# 9_PCIE3.net
KiCad netlist of a schematic drawn in Altium Designer
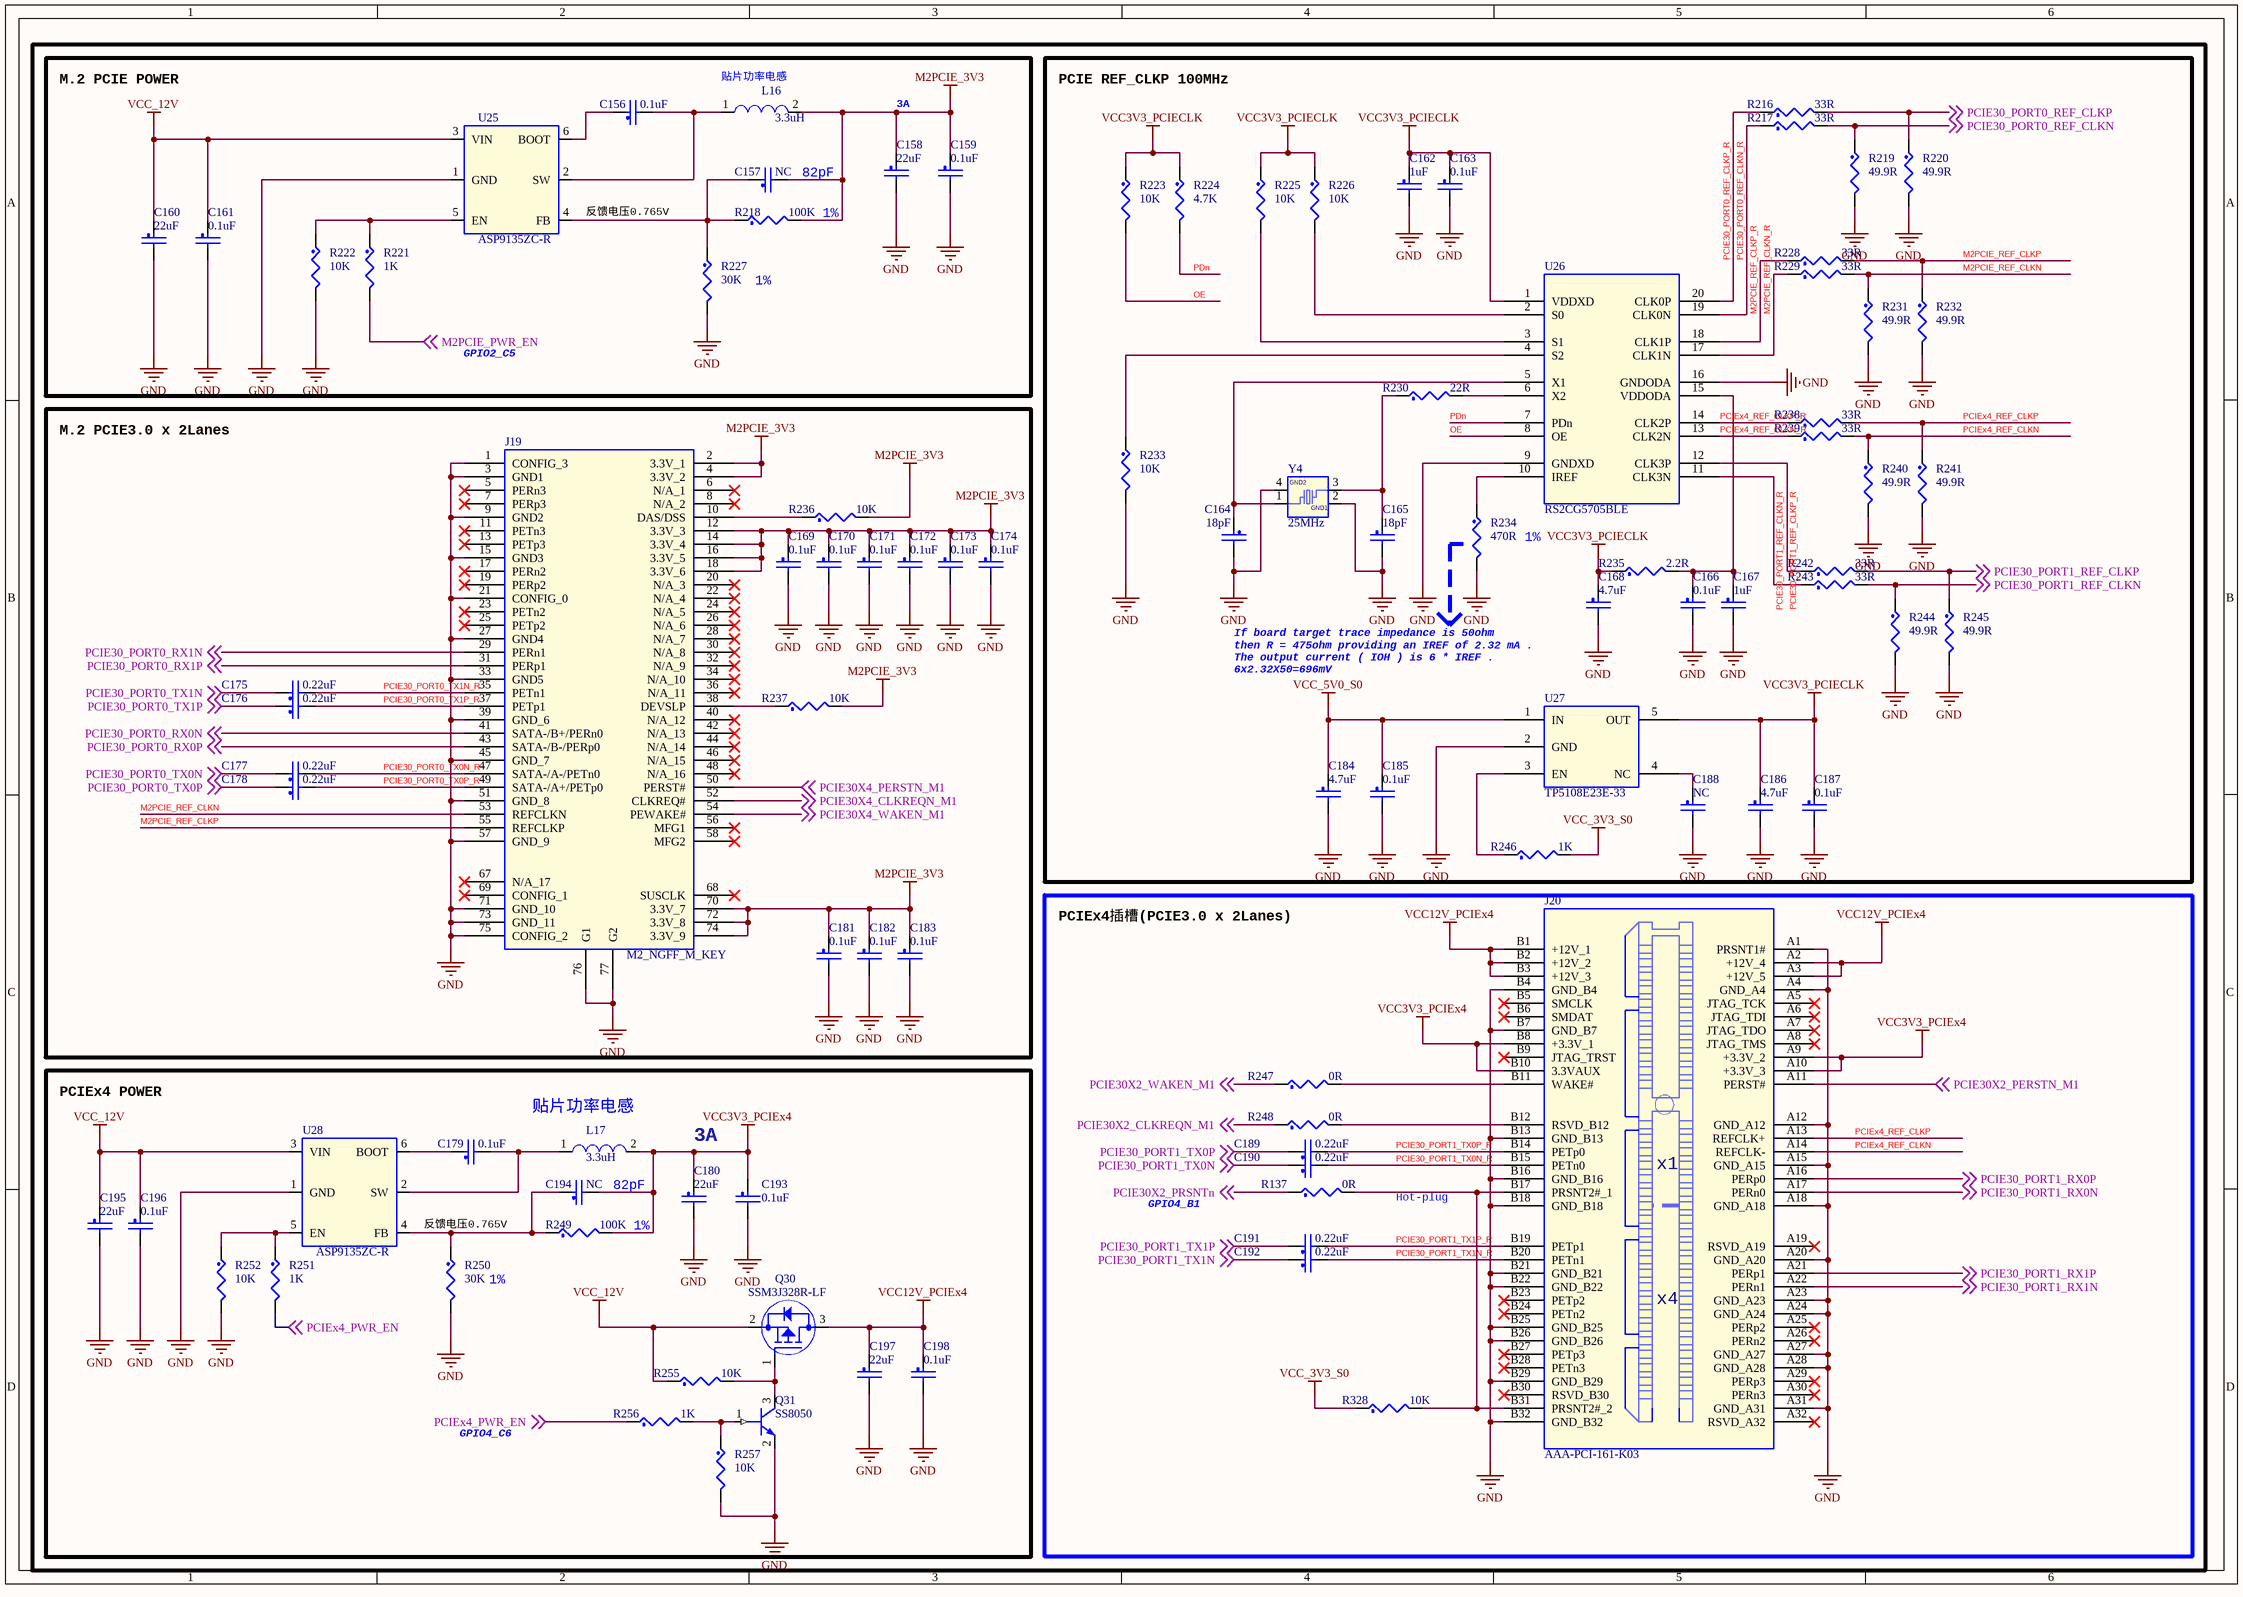
[diagram p0: 9.PCIE3.SchDoc]

(export (version "E")
  (design (tool "Eeschema 10.0.6"))
  (components
    (comp (ref "C156")
      (value "0.1uF")
      (footprint "0.PCB1:C0402")
      (libsource (lib "RK3588底板") (part "CAP_NP"))
    )
    (comp (ref "C157") (value "NC") (footprint "0.PCB1:C0402") (libsource (lib "RK3588底板") (part "CAP_NP")))
    (comp (ref "C158") (value "22uF") (footprint "0.PCB1:C0603") (libsource (lib "RK3588底板") (part "CAP_NP")))
    (comp (ref "C159")
      (value "0.1uF")
      (footprint "0.PCB1:C0402")
      (libsource (lib "RK3588底板") (part "CAP_NP"))
    )
    (comp (ref "C160") (value "22uF") (footprint "0.PCB1:C0603") (libsource (lib "RK3588底板") (part "CAP_NP")))
    (comp (ref "C161")
      (value "0.1uF")
      (footprint "0.PCB1:C0402")
      (libsource (lib "RK3588底板") (part "CAP_NP"))
    )
    (comp (ref "C162") (value "1uF") (footprint "0.PCB1:C0402") (libsource (lib "RK3588底板") (part "CAP_NP")))
    (comp (ref "C163")
      (value "0.1uF")
      (footprint "0.PCB1:C0402")
      (libsource (lib "RK3588底板") (part "CAP_NP"))
    )
    (comp (ref "C164") (value "18pF") (footprint "0.PCB1:C0402") (libsource (lib "RK3588底板") (part "CAP_NP")))
    (comp (ref "C165") (value "18pF") (footprint "0.PCB1:C0402") (libsource (lib "RK3588底板") (part "CAP_NP")))
    (comp (ref "C166")
      (value "0.1uF")
      (footprint "0.PCB1:C0402")
      (libsource (lib "RK3588底板") (part "CAP_NP"))
    )
    (comp (ref "C167") (value "1uF") (footprint "0.PCB1:C0402") (libsource (lib "RK3588底板") (part "CAP_NP")))
    (comp (ref "C168")
      (value "4.7uF")
      (footprint "0.PCB1:C0402")
      (libsource (lib "RK3588底板") (part "CAP_NP"))
    )
    (comp (ref "C169")
      (value "0.1uF")
      (footprint "0.PCB1:C0402")
      (libsource (lib "RK3588底板") (part "CAP_NP"))
    )
    (comp (ref "C170")
      (value "0.1uF")
      (footprint "0.PCB1:C0402")
      (libsource (lib "RK3588底板") (part "CAP_NP"))
    )
    (comp (ref "C171")
      (value "0.1uF")
      (footprint "0.PCB1:C0402")
      (libsource (lib "RK3588底板") (part "CAP_NP"))
    )
    (comp (ref "C172")
      (value "0.1uF")
      (footprint "0.PCB1:C0402")
      (libsource (lib "RK3588底板") (part "CAP_NP"))
    )
    (comp (ref "C173")
      (value "0.1uF")
      (footprint "0.PCB1:C0402")
      (libsource (lib "RK3588底板") (part "CAP_NP"))
    )
    (comp (ref "C174")
      (value "0.1uF")
      (footprint "0.PCB1:C0402")
      (libsource (lib "RK3588底板") (part "CAP_NP"))
    )
    (comp (ref "C175")
      (value "0.22uF")
      (footprint "0.PCB1:C0402")
      (libsource (lib "RK3588底板") (part "CAP_NP"))
    )
    (comp (ref "C176")
      (value "0.22uF")
      (footprint "0.PCB1:C0402")
      (libsource (lib "RK3588底板") (part "CAP_NP"))
    )
    (comp (ref "C177")
      (value "0.22uF")
      (footprint "0.PCB1:C0402")
      (libsource (lib "RK3588底板") (part "CAP_NP"))
    )
    (comp (ref "C178")
      (value "0.22uF")
      (footprint "0.PCB1:C0402")
      (libsource (lib "RK3588底板") (part "CAP_NP"))
    )
    (comp (ref "C179")
      (value "0.1uF")
      (footprint "0.PCB1:C0402")
      (libsource (lib "RK3588底板") (part "CAP_NP"))
    )
    (comp (ref "C180") (value "22uF") (footprint "0.PCB1:C0603") (libsource (lib "RK3588底板") (part "CAP_NP")))
    (comp (ref "C181")
      (value "0.1uF")
      (footprint "0.PCB1:C0402")
      (libsource (lib "RK3588底板") (part "CAP_NP"))
    )
    (comp (ref "C182")
      (value "0.1uF")
      (footprint "0.PCB1:C0402")
      (libsource (lib "RK3588底板") (part "CAP_NP"))
    )
    (comp (ref "C183")
      (value "0.1uF")
      (footprint "0.PCB1:C0402")
      (libsource (lib "RK3588底板") (part "CAP_NP"))
    )
    (comp (ref "C184")
      (value "4.7uF")
      (footprint "0.PCB1:C0402")
      (libsource (lib "RK3588底板") (part "CAP_NP"))
    )
    (comp (ref "C185")
      (value "0.1uF")
      (footprint "0.PCB1:C0402")
      (libsource (lib "RK3588底板") (part "CAP_NP"))
    )
    (comp (ref "C186")
      (value "4.7uF")
      (footprint "0.PCB1:C0402")
      (libsource (lib "RK3588底板") (part "CAP_NP"))
    )
    (comp (ref "C187")
      (value "0.1uF")
      (footprint "0.PCB1:C0402")
      (libsource (lib "RK3588底板") (part "CAP_NP"))
    )
    (comp (ref "C188") (value "NC") (footprint "0.PCB1:C0402") (libsource (lib "RK3588底板") (part "CAP_NP")))
    (comp (ref "C189")
      (value "0.22uF")
      (footprint "0.PCB1:C0402")
      (libsource (lib "RK3588底板") (part "CAP_NP"))
    )
    (comp (ref "C190")
      (value "0.22uF")
      (footprint "0.PCB1:C0402")
      (libsource (lib "RK3588底板") (part "CAP_NP"))
    )
    (comp (ref "C191")
      (value "0.22uF")
      (footprint "0.PCB1:C0402")
      (libsource (lib "RK3588底板") (part "CAP_NP"))
    )
    (comp (ref "C192")
      (value "0.22uF")
      (footprint "0.PCB1:C0402")
      (libsource (lib "RK3588底板") (part "CAP_NP"))
    )
    (comp (ref "C193")
      (value "0.1uF")
      (footprint "0.PCB1:C0402")
      (libsource (lib "RK3588底板") (part "CAP_NP"))
    )
    (comp (ref "C194") (value "NC") (footprint "0.PCB1:C0402") (libsource (lib "RK3588底板") (part "CAP_NP")))
    (comp (ref "C195") (value "22uF") (footprint "0.PCB1:C0603") (libsource (lib "RK3588底板") (part "CAP_NP")))
    (comp (ref "C196")
      (value "0.1uF")
      (footprint "0.PCB1:C0402")
      (libsource (lib "RK3588底板") (part "CAP_NP"))
    )
    (comp (ref "C197") (value "22uF") (footprint "0.PCB1:C0603") (libsource (lib "RK3588底板") (part "CAP_NP")))
    (comp (ref "C198")
      (value "0.1uF")
      (footprint "0.PCB1:C0402")
      (libsource (lib "RK3588底板") (part "CAP_NP"))
    )
    (comp (ref "J19")
      (value "M2_NGFF_M_KEY")
      (footprint "0.PCB1:M2_NGFF_M_KEY")
      (libsource (lib "RK3588底板") (part "M2_NGFF_M_KEY"))
    )
    (comp (ref "J20")
      (value "AAA-PCI-161-K03")
      (footprint "0.PCB1:PCIE_64PIN_1R00")
      (libsource (lib "RK3588底板") (part "PCIEX4_64P"))
    )
    (comp (ref "L16") (value "3.3uH") (footprint "0.PCB1:l4520") (libsource (lib "RK3588底板") (part "IND")))
    (comp (ref "L17") (value "3.3uH") (footprint "0.PCB1:l4520") (libsource (lib "RK3588底板") (part "IND")))
    (comp (ref "Q30")
      (value "SSM3J328R-LF")
      (footprint "0.PCB1:SOT23")
      (libsource (lib "RK3588底板") (part "MOSFET_P"))
    )
    (comp (ref "Q31") (value "SS8050") (footprint "0.PCB1:SOT23") (libsource (lib "RK3588底板") (part "NPN")))
    (comp (ref "R137") (value "0R") (footprint "0.PCB1:R0402") (libsource (lib "RK3588底板") (part "RES")))
    (comp (ref "R216") (value "33R") (footprint "0.PCB1:R0402") (libsource (lib "RK3588底板") (part "RES")))
    (comp (ref "R217") (value "33R") (footprint "0.PCB1:R0402") (libsource (lib "RK3588底板") (part "RES")))
    (comp (ref "R218") (value "100K") (footprint "0.PCB1:R0402") (libsource (lib "RK3588底板") (part "RES")))
    (comp (ref "R219") (value "49.9R") (footprint "0.PCB1:R0402") (libsource (lib "RK3588底板") (part "RES")))
    (comp (ref "R220") (value "49.9R") (footprint "0.PCB1:R0402") (libsource (lib "RK3588底板") (part "RES")))
    (comp (ref "R221") (value "1K") (footprint "0.PCB1:R0402") (libsource (lib "RK3588底板") (part "RES")))
    (comp (ref "R222") (value "10K") (footprint "0.PCB1:R0402") (libsource (lib "RK3588底板") (part "RES")))
    (comp (ref "R223") (value "10K") (footprint "0.PCB1:R0402") (libsource (lib "RK3588底板") (part "RES")))
    (comp (ref "R224") (value "4.7K") (footprint "0.PCB1:R0402") (libsource (lib "RK3588底板") (part "RES")))
    (comp (ref "R225") (value "10K") (footprint "0.PCB1:R0402") (libsource (lib "RK3588底板") (part "RES")))
    (comp (ref "R226") (value "10K") (footprint "0.PCB1:R0402") (libsource (lib "RK3588底板") (part "RES")))
    (comp (ref "R227") (value "30K") (footprint "0.PCB1:R0402") (libsource (lib "RK3588底板") (part "RES")))
    (comp (ref "R228") (value "33R") (footprint "0.PCB1:R0402") (libsource (lib "RK3588底板") (part "RES")))
    (comp (ref "R229") (value "33R") (footprint "0.PCB1:R0402") (libsource (lib "RK3588底板") (part "RES")))
    (comp (ref "R230") (value "22R") (footprint "0.PCB1:R0402") (libsource (lib "RK3588底板") (part "RES")))
    (comp (ref "R231") (value "49.9R") (footprint "0.PCB1:R0402") (libsource (lib "RK3588底板") (part "RES")))
    (comp (ref "R232") (value "49.9R") (footprint "0.PCB1:R0402") (libsource (lib "RK3588底板") (part "RES")))
    (comp (ref "R233") (value "10K") (footprint "0.PCB1:R0402") (libsource (lib "RK3588底板") (part "RES")))
    (comp (ref "R234") (value "470R") (footprint "0.PCB1:R0402") (libsource (lib "RK3588底板") (part "RES")))
    (comp (ref "R235") (value "2.2R") (footprint "0.PCB1:R0402") (libsource (lib "RK3588底板") (part "RES")))
    (comp (ref "R236") (value "10K") (footprint "0.PCB1:R0402") (libsource (lib "RK3588底板") (part "RES")))
    (comp (ref "R237") (value "10K") (footprint "0.PCB1:R0402") (libsource (lib "RK3588底板") (part "RES")))
    (comp (ref "R238") (value "33R") (footprint "0.PCB1:R0402") (libsource (lib "RK3588底板") (part "RES")))
    (comp (ref "R239") (value "33R") (footprint "0.PCB1:R0402") (libsource (lib "RK3588底板") (part "RES")))
    (comp (ref "R240") (value "49.9R") (footprint "0.PCB1:R0402") (libsource (lib "RK3588底板") (part "RES")))
    (comp (ref "R241") (value "49.9R") (footprint "0.PCB1:R0402") (libsource (lib "RK3588底板") (part "RES")))
    (comp (ref "R242") (value "33R") (footprint "0.PCB1:R0402") (libsource (lib "RK3588底板") (part "RES")))
    (comp (ref "R243") (value "33R") (footprint "0.PCB1:R0402") (libsource (lib "RK3588底板") (part "RES")))
    (comp (ref "R244") (value "49.9R") (footprint "0.PCB1:R0402") (libsource (lib "RK3588底板") (part "RES")))
    (comp (ref "R245") (value "49.9R") (footprint "0.PCB1:R0402") (libsource (lib "RK3588底板") (part "RES")))
    (comp (ref "R246") (value "1K") (footprint "0.PCB1:R0402") (libsource (lib "RK3588底板") (part "RES")))
    (comp (ref "R247") (value "0R") (footprint "0.PCB1:R0402") (libsource (lib "RK3588底板") (part "RES")))
    (comp (ref "R248") (value "0R") (footprint "0.PCB1:R0402") (libsource (lib "RK3588底板") (part "RES")))
    (comp (ref "R249") (value "100K") (footprint "0.PCB1:R0402") (libsource (lib "RK3588底板") (part "RES")))
    (comp (ref "R250") (value "30K") (footprint "0.PCB1:R0402") (libsource (lib "RK3588底板") (part "RES")))
    (comp (ref "R251") (value "1K") (footprint "0.PCB1:R0402") (libsource (lib "RK3588底板") (part "RES")))
    (comp (ref "R252") (value "10K") (footprint "0.PCB1:R0402") (libsource (lib "RK3588底板") (part "RES")))
    (comp (ref "R255") (value "10K") (footprint "0.PCB1:R0402") (libsource (lib "RK3588底板") (part "RES")))
    (comp (ref "R256") (value "1K") (footprint "0.PCB1:R0402") (libsource (lib "RK3588底板") (part "RES")))
    (comp (ref "R257") (value "10K") (footprint "0.PCB1:R0402") (libsource (lib "RK3588底板") (part "RES")))
    (comp (ref "R328") (value "10K") (footprint "0.PCB1:R0402") (libsource (lib "RK3588底板") (part "RES")))
    (comp (ref "U25")
      (value "ASP9135ZC-R")
      (footprint "0.PCB1:SOT23_6")
      (libsource (lib "RK3588底板") (part "TP6327GS6"))
    )
    (comp (ref "U26")
      (value "RS2CG5705BLE")
      (footprint "0.PCB1:TSSOP20")
      (libsource (lib "RK3588底板") (part "PI6C557-05BLE"))
    )
    (comp (ref "U27")
      (value "TP5108E23E-33")
      (footprint "0.PCB1:SOT23-5")
      (libsource (lib "RK3588底板") (part "LDO_PT5108"))
    )
    (comp (ref "U28")
      (value "ASP9135ZC-R")
      (footprint "0.PCB1:SOT23_6")
      (libsource (lib "RK3588底板") (part "TP6327GS6"))
    )
    (comp (ref "Y4")
      (value "25MHz")
      (footprint "0.PCB1:3225")
      (libsource (lib "RK3588底板") (part "CRYSTAL_4P"))
    )
  )
  (nets
    (net (code "1") (name "/M2PCIE_REF_CLKN") (class "Default")
      (node (ref "J19") (pin "53") (pinfunction "REFCLKN_53") (pintype "passive"))
      (node (ref "R229") (pin "2") (pinfunction "2_2") (pintype "passive"))
      (node (ref "R231") (pin "1") (pinfunction "1_1") (pintype "passive"))
    )
    (net (code "2") (name "/M2PCIE_REF_CLKN_R") (class "Default")
      (node (ref "R229") (pin "1") (pinfunction "1_1") (pintype "passive"))
      (node (ref "U26") (pin "17") (pinfunction "CLK1N_17") (pintype "passive"))
    )
    (net (code "3") (name "/M2PCIE_REF_CLKP") (class "Default")
      (node (ref "J19") (pin "55") (pinfunction "REFCLKP_55") (pintype "passive"))
      (node (ref "R228") (pin "2") (pinfunction "2_2") (pintype "passive"))
      (node (ref "R232") (pin "1") (pinfunction "1_1") (pintype "passive"))
    )
    (net (code "4") (name "/M2PCIE_REF_CLKP_R") (class "Default")
      (node (ref "R228") (pin "1") (pinfunction "1_1") (pintype "passive"))
      (node (ref "U26") (pin "18") (pinfunction "CLK1P_18") (pintype "passive"))
    )
    (net (code "5") (name "/OE") (class "Default")
      (node (ref "R223") (pin "2") (pinfunction "2_2") (pintype "passive"))
      (node (ref "U26") (pin "8") (pinfunction "OE_8") (pintype "passive"))
    )
    (net (code "6") (name "/PCIE30_PORT0_REF_CLKN_R") (class "Default")
      (node (ref "R217") (pin "1") (pinfunction "1_1") (pintype "passive"))
      (node (ref "U26") (pin "19") (pinfunction "CLK0N_19") (pintype "passive"))
    )
    (net (code "7") (name "/PCIE30_PORT0_REF_CLKP_R") (class "Default")
      (node (ref "R216") (pin "1") (pinfunction "1_1") (pintype "passive"))
      (node (ref "U26") (pin "20") (pinfunction "CLK0P_20") (pintype "passive"))
    )
    (net (code "8") (name "/PCIE30_PORT0_TX0N_R") (class "Default")
      (node (ref "C177") (pin "2") (pinfunction "2_2") (pintype "passive"))
      (node (ref "J19") (pin "47") (pinfunction "SATA-/A-/PETn0_47") (pintype "passive"))
    )
    (net (code "9") (name "/PCIE30_PORT0_TX0P_R") (class "Default")
      (node (ref "C178") (pin "2") (pinfunction "2_2") (pintype "passive"))
      (node (ref "J19") (pin "49") (pinfunction "SATA-/A+/PETp0_49") (pintype "passive"))
    )
    (net (code "10") (name "/PCIE30_PORT0_TX1N_R") (class "Default")
      (node (ref "C175") (pin "2") (pinfunction "2_2") (pintype "passive"))
      (node (ref "J19") (pin "35") (pinfunction "PETn1_35") (pintype "passive"))
    )
    (net (code "11") (name "/PCIE30_PORT0_TX1P_R") (class "Default")
      (node (ref "C176") (pin "2") (pinfunction "2_2") (pintype "passive"))
      (node (ref "J19") (pin "37") (pinfunction "PETp1_37") (pintype "passive"))
    )
    (net (code "12") (name "/PCIE30_PORT1_REF_CLKN_R") (class "Default")
      (node (ref "R243") (pin "1") (pinfunction "1_1") (pintype "passive"))
      (node (ref "U26") (pin "11") (pinfunction "CLK3N_11") (pintype "passive"))
    )
    (net (code "13") (name "/PCIE30_PORT1_REF_CLKP_R") (class "Default")
      (node (ref "R242") (pin "1") (pinfunction "1_1") (pintype "passive"))
      (node (ref "U26") (pin "12") (pinfunction "CLK3P_12") (pintype "passive"))
    )
    (net (code "14") (name "/PCIE30_PORT1_TX0N_R") (class "Default")
      (node (ref "C190") (pin "2") (pinfunction "2_2") (pintype "passive"))
      (node (ref "J20") (pin "B15") (pinfunction "PETn0_B15") (pintype "passive"))
    )
    (net (code "15") (name "/PCIE30_PORT1_TX0P_R") (class "Default")
      (node (ref "C189") (pin "2") (pinfunction "2_2") (pintype "passive"))
      (node (ref "J20") (pin "B14") (pinfunction "PETp0_B14") (pintype "passive"))
    )
    (net (code "16") (name "/PCIE30_PORT1_TX1N_R") (class "Default")
      (node (ref "C192") (pin "2") (pinfunction "2_2") (pintype "passive"))
      (node (ref "J20") (pin "B20") (pinfunction "PETn1_B20") (pintype "passive"))
    )
    (net (code "17") (name "/PCIE30_PORT1_TX1P_R") (class "Default")
      (node (ref "C191") (pin "2") (pinfunction "2_2") (pintype "passive"))
      (node (ref "J20") (pin "B19") (pinfunction "PETp1_B19") (pintype "passive"))
    )
    (net (code "18") (name "/PCIEx4_REF_CLKN") (class "Default")
      (node (ref "J20") (pin "A14") (pinfunction "REFCLK-_A14") (pintype "passive"))
      (node (ref "R239") (pin "2") (pinfunction "2_2") (pintype "passive"))
      (node (ref "R240") (pin "1") (pinfunction "1_1") (pintype "passive"))
    )
    (net (code "19") (name "/PCIEx4_REF_CLKN_R") (class "Default")
      (node (ref "R239") (pin "1") (pinfunction "1_1") (pintype "passive"))
      (node (ref "U26") (pin "13") (pinfunction "CLK2N_13") (pintype "passive"))
    )
    (net (code "20") (name "/PCIEx4_REF_CLKP") (class "Default")
      (node (ref "J20") (pin "A13") (pinfunction "REFCLK+_A13") (pintype "passive"))
      (node (ref "R238") (pin "2") (pinfunction "2_2") (pintype "passive"))
      (node (ref "R241") (pin "1") (pinfunction "1_1") (pintype "passive"))
    )
    (net (code "21") (name "/PCIEx4_REF_CLKP_R") (class "Default")
      (node (ref "R238") (pin "1") (pinfunction "1_1") (pintype "passive"))
      (node (ref "U26") (pin "14") (pinfunction "CLK2P_14") (pintype "passive"))
    )
    (net (code "22") (name "/PDn") (class "Default")
      (node (ref "R224") (pin "2") (pinfunction "2_2") (pintype "passive"))
      (node (ref "U26") (pin "7") (pinfunction "PDn_7") (pintype "passive"))
    )
    (net (code "23") (name "GND") (class "Default")
      (node (ref "C158") (pin "2") (pinfunction "2_2") (pintype "passive"))
      (node (ref "C159") (pin "2") (pinfunction "2_2") (pintype "passive"))
      (node (ref "C160") (pin "2") (pinfunction "2_2") (pintype "passive"))
      (node (ref "C161") (pin "2") (pinfunction "2_2") (pintype "passive"))
      (node (ref "C162") (pin "2") (pinfunction "2_2") (pintype "passive"))
      (node (ref "C163") (pin "2") (pinfunction "2_2") (pintype "passive"))
      (node (ref "C164") (pin "2") (pinfunction "2_2") (pintype "passive"))
      (node (ref "C165") (pin "2") (pinfunction "2_2") (pintype "passive"))
      (node (ref "C166") (pin "2") (pinfunction "2_2") (pintype "passive"))
      (node (ref "C167") (pin "2") (pinfunction "2_2") (pintype "passive"))
      (node (ref "C168") (pin "2") (pinfunction "2_2") (pintype "passive"))
      (node (ref "C169") (pin "2") (pinfunction "2_2") (pintype "passive"))
      (node (ref "C170") (pin "2") (pinfunction "2_2") (pintype "passive"))
      (node (ref "C171") (pin "2") (pinfunction "2_2") (pintype "passive"))
      (node (ref "C172") (pin "2") (pinfunction "2_2") (pintype "passive"))
      (node (ref "C173") (pin "2") (pinfunction "2_2") (pintype "passive"))
      (node (ref "C174") (pin "2") (pinfunction "2_2") (pintype "passive"))
      (node (ref "C180") (pin "2") (pinfunction "2_2") (pintype "passive"))
      (node (ref "C181") (pin "2") (pinfunction "2_2") (pintype "passive"))
      (node (ref "C182") (pin "2") (pinfunction "2_2") (pintype "passive"))
      (node (ref "C183") (pin "2") (pinfunction "2_2") (pintype "passive"))
      (node (ref "C184") (pin "2") (pinfunction "2_2") (pintype "passive"))
      (node (ref "C185") (pin "2") (pinfunction "2_2") (pintype "passive"))
      (node (ref "C186") (pin "2") (pinfunction "2_2") (pintype "passive"))
      (node (ref "C187") (pin "2") (pinfunction "2_2") (pintype "passive"))
      (node (ref "C188") (pin "2") (pinfunction "2_2") (pintype "passive"))
      (node (ref "C193") (pin "2") (pinfunction "2_2") (pintype "passive"))
      (node (ref "C195") (pin "2") (pinfunction "2_2") (pintype "passive"))
      (node (ref "C196") (pin "2") (pinfunction "2_2") (pintype "passive"))
      (node (ref "C197") (pin "2") (pinfunction "2_2") (pintype "passive"))
      (node (ref "C198") (pin "2") (pinfunction "2_2") (pintype "passive"))
      (node (ref "J19") (pin "1") (pinfunction "CONFIG_3_1") (pintype "passive"))
      (node (ref "J19") (pin "15") (pinfunction "GND3_15") (pintype "passive"))
      (node (ref "J19") (pin "21") (pinfunction "CONFIG_0_21") (pintype "passive"))
      (node (ref "J19") (pin "27") (pinfunction "GND4_27") (pintype "passive"))
      (node (ref "J19") (pin "3") (pinfunction "GND1_3") (pintype "passive"))
      (node (ref "J19") (pin "33") (pinfunction "GND5_33") (pintype "passive"))
      (node (ref "J19") (pin "39") (pinfunction "GND_6_39") (pintype "passive"))
      (node (ref "J19") (pin "45") (pinfunction "GND_7_45") (pintype "passive"))
      (node (ref "J19") (pin "51") (pinfunction "GND_8_51") (pintype "passive"))
      (node (ref "J19") (pin "57") (pinfunction "GND_9_57") (pintype "passive"))
      (node (ref "J19") (pin "71") (pinfunction "GND_10_71") (pintype "passive"))
      (node (ref "J19") (pin "73") (pinfunction "GND_11_73") (pintype "passive"))
      (node (ref "J19") (pin "75") (pinfunction "CONFIG_2_75") (pintype "passive"))
      (node (ref "J19") (pin "76") (pinfunction "G1_76") (pintype "passive"))
      (node (ref "J19") (pin "77") (pinfunction "G2_77") (pintype "passive"))
      (node (ref "J19") (pin "9") (pinfunction "GND2_9") (pintype "passive"))
      (node (ref "J20") (pin "A1") (pinfunction "PRSNT1#_A1") (pintype "passive"))
      (node (ref "J20") (pin "A12") (pinfunction "GND_A12_A12") (pintype "passive"))
      (node (ref "J20") (pin "A15") (pinfunction "GND_A15_A15") (pintype "passive"))
      (node (ref "J20") (pin "A18") (pinfunction "GND_A18_A18") (pintype "passive"))
      (node (ref "J20") (pin "A20") (pinfunction "GND_A20_A20") (pintype "passive"))
      (node (ref "J20") (pin "A23") (pinfunction "GND_A23_A23") (pintype "passive"))
      (node (ref "J20") (pin "A24") (pinfunction "GND_A24_A24") (pintype "passive"))
      (node (ref "J20") (pin "A27") (pinfunction "GND_A27_A27") (pintype "passive"))
      (node (ref "J20") (pin "A28") (pinfunction "GND_A28_A28") (pintype "passive"))
      (node (ref "J20") (pin "A31") (pinfunction "GND_A31_A31") (pintype "passive"))
      (node (ref "J20") (pin "A4") (pinfunction "GND_A4_A4") (pintype "passive"))
      (node (ref "J20") (pin "B13") (pinfunction "GND_B13_B13") (pintype "passive"))
      (node (ref "J20") (pin "B16") (pinfunction "GND_B16_B16") (pintype "passive"))
      (node (ref "J20") (pin "B18") (pinfunction "GND_B18_B18") (pintype "passive"))
      (node (ref "J20") (pin "B21") (pinfunction "GND_B21_B21") (pintype "passive"))
      (node (ref "J20") (pin "B22") (pinfunction "GND_B22_B22") (pintype "passive"))
      (node (ref "J20") (pin "B25") (pinfunction "GND_B25_B25") (pintype "passive"))
      (node (ref "J20") (pin "B26") (pinfunction "GND_B26_B26") (pintype "passive"))
      (node (ref "J20") (pin "B29") (pinfunction "GND_B29_B29") (pintype "passive"))
      (node (ref "J20") (pin "B32") (pinfunction "GND_B32_B32") (pintype "passive"))
      (node (ref "J20") (pin "B4") (pinfunction "GND_B4_B4") (pintype "passive"))
      (node (ref "J20") (pin "B7") (pinfunction "GND_B7_B7") (pintype "passive"))
      (node (ref "Q31") (pin "2") (pinfunction "EMITTER_2") (pintype "passive"))
      (node (ref "R219") (pin "2") (pinfunction "2_2") (pintype "passive"))
      (node (ref "R220") (pin "2") (pinfunction "2_2") (pintype "passive"))
      (node (ref "R222") (pin "2") (pinfunction "2_2") (pintype "passive"))
      (node (ref "R227") (pin "2") (pinfunction "2_2") (pintype "passive"))
      (node (ref "R231") (pin "2") (pinfunction "2_2") (pintype "passive"))
      (node (ref "R232") (pin "2") (pinfunction "2_2") (pintype "passive"))
      (node (ref "R233") (pin "2") (pinfunction "2_2") (pintype "passive"))
      (node (ref "R234") (pin "2") (pinfunction "2_2") (pintype "passive"))
      (node (ref "R240") (pin "2") (pinfunction "2_2") (pintype "passive"))
      (node (ref "R241") (pin "2") (pinfunction "2_2") (pintype "passive"))
      (node (ref "R244") (pin "2") (pinfunction "2_2") (pintype "passive"))
      (node (ref "R245") (pin "2") (pinfunction "2_2") (pintype "passive"))
      (node (ref "R250") (pin "2") (pinfunction "2_2") (pintype "passive"))
      (node (ref "R252") (pin "2") (pinfunction "2_2") (pintype "passive"))
      (node (ref "R257") (pin "2") (pinfunction "2_2") (pintype "passive"))
      (node (ref "U25") (pin "1") (pinfunction "GND_1") (pintype "passive"))
      (node (ref "U26") (pin "16") (pinfunction "GNDODA_16") (pintype "passive"))
      (node (ref "U26") (pin "9") (pinfunction "GNDXD_9") (pintype "passive"))
      (node (ref "U27") (pin "2") (pinfunction "GND_2") (pintype "passive"))
      (node (ref "U28") (pin "1") (pinfunction "GND_1") (pintype "passive"))
      (node (ref "Y4") (pin "2") (pinfunction "GND1_2") (pintype "power_in"))
      (node (ref "Y4") (pin "4") (pinfunction "GND2_4") (pintype "power_in"))
    )
    (net (code "24") (name "M2PCIE_3V3") (class "Default")
      (node (ref "C157") (pin "2") (pinfunction "2_2") (pintype "passive"))
      (node (ref "C158") (pin "1") (pinfunction "1_1") (pintype "passive"))
      (node (ref "C159") (pin "1") (pinfunction "1_1") (pintype "passive"))
      (node (ref "C169") (pin "1") (pinfunction "1_1") (pintype "passive"))
      (node (ref "C170") (pin "1") (pinfunction "1_1") (pintype "passive"))
      (node (ref "C171") (pin "1") (pinfunction "1_1") (pintype "passive"))
      (node (ref "C172") (pin "1") (pinfunction "1_1") (pintype "passive"))
      (node (ref "C173") (pin "1") (pinfunction "1_1") (pintype "passive"))
      (node (ref "C174") (pin "1") (pinfunction "1_1") (pintype "passive"))
      (node (ref "C181") (pin "1") (pinfunction "1_1") (pintype "passive"))
      (node (ref "C182") (pin "1") (pinfunction "1_1") (pintype "passive"))
      (node (ref "C183") (pin "1") (pinfunction "1_1") (pintype "passive"))
      (node (ref "J19") (pin "12") (pinfunction "3.3V_3_12") (pintype "passive"))
      (node (ref "J19") (pin "14") (pinfunction "3.3V_4_14") (pintype "passive"))
      (node (ref "J19") (pin "16") (pinfunction "3.3V_5_16") (pintype "passive"))
      (node (ref "J19") (pin "18") (pinfunction "3.3V_6_18") (pintype "passive"))
      (node (ref "J19") (pin "2") (pinfunction "3.3V_1_2") (pintype "passive"))
      (node (ref "J19") (pin "4") (pinfunction "3.3V_2_4") (pintype "passive"))
      (node (ref "J19") (pin "70") (pinfunction "3.3V_7_70") (pintype "passive"))
      (node (ref "J19") (pin "72") (pinfunction "3.3V_8_72") (pintype "passive"))
      (node (ref "J19") (pin "74") (pinfunction "3.3V_9_74") (pintype "passive"))
      (node (ref "L16") (pin "2") (pinfunction "2_2") (pintype "passive"))
      (node (ref "R218") (pin "2") (pinfunction "2_2") (pintype "passive"))
      (node (ref "R236") (pin "2") (pinfunction "2_2") (pintype "passive"))
      (node (ref "R237") (pin "2") (pinfunction "2_2") (pintype "passive"))
    )
    (net (code "25") (name "M2PCIE_PWR_EN") (class "Default")
      (node (ref "R221") (pin "2") (pinfunction "2_2") (pintype "passive"))
    )
    (net (code "26") (name "Net-(C165-Pad1)") (class "Default")
      (node (ref "C165") (pin "1") (pinfunction "1_1") (pintype "passive"))
      (node (ref "R230") (pin "1") (pinfunction "1_1") (pintype "passive"))
      (node (ref "Y4") (pin "3") (pinfunction "3_3") (pintype "passive"))
    )
    (net (code "27") (name "Net-(J19-DAS{slash}DSS)") (class "Default")
      (node (ref "J19") (pin "10") (pinfunction "DAS/DSS_10") (pintype "passive"))
      (node (ref "R236") (pin "1") (pinfunction "1_1") (pintype "passive"))
    )
    (net (code "28") (name "Net-(J19-DEVSLP)") (class "Default")
      (node (ref "J19") (pin "38") (pinfunction "DEVSLP_38") (pintype "passive"))
      (node (ref "R237") (pin "1") (pinfunction "1_1") (pintype "passive"))
    )
    (net (code "29") (name "Net-(J20-PRSNT2#_1)") (class "Default")
      (node (ref "J20") (pin "B17") (pinfunction "PRSNT2#_1_B17") (pintype "passive"))
      (node (ref "J20") (pin "B31") (pinfunction "PRSNT2#_2_B31") (pintype "passive"))
      (node (ref "R137") (pin "2") (pinfunction "2_2") (pintype "passive"))
      (node (ref "R328") (pin "2") (pinfunction "2_2") (pintype "passive"))
    )
    (net (code "30") (name "Net-(J20-RSVD_B12)") (class "Default")
      (node (ref "J20") (pin "B12") (pinfunction "RSVD_B12_B12") (pintype "passive"))
      (node (ref "R248") (pin "2") (pinfunction "2_2") (pintype "passive"))
    )
    (net (code "31") (name "Net-(J20-WAKE#)") (class "Default")
      (node (ref "J20") (pin "B11") (pinfunction "WAKE#_B11") (pintype "passive"))
      (node (ref "R247") (pin "2") (pinfunction "2_2") (pintype "passive"))
    )
    (net (code "32") (name "Net-(Q30-GATE)") (class "Default")
      (node (ref "Q30") (pin "1") (pinfunction "GATE_1") (pintype "passive"))
      (node (ref "Q31") (pin "3") (pinfunction "COLLECTOR_3") (pintype "passive"))
      (node (ref "R255") (pin "2") (pinfunction "2_2") (pintype "passive"))
    )
    (net (code "33") (name "Net-(Q31-BASE)") (class "Default")
      (node (ref "Q31") (pin "1") (pinfunction "BASE_1") (pintype "input"))
      (node (ref "R256") (pin "2") (pinfunction "2_2") (pintype "passive"))
      (node (ref "R257") (pin "1") (pinfunction "1_1") (pintype "passive"))
    )
    (net (code "34") (name "Net-(U25-BOOT)") (class "Default")
      (node (ref "C156") (pin "1") (pinfunction "1_1") (pintype "passive"))
      (node (ref "U25") (pin "6") (pinfunction "BOOT_6") (pintype "passive"))
    )
    (net (code "35") (name "Net-(U25-EN)") (class "Default")
      (node (ref "R221") (pin "1") (pinfunction "1_1") (pintype "passive"))
      (node (ref "R222") (pin "1") (pinfunction "1_1") (pintype "passive"))
      (node (ref "U25") (pin "5") (pinfunction "EN_5") (pintype "passive"))
    )
    (net (code "36") (name "Net-(U25-FB)") (class "Default")
      (node (ref "C157") (pin "1") (pinfunction "1_1") (pintype "passive"))
      (node (ref "R218") (pin "1") (pinfunction "1_1") (pintype "passive"))
      (node (ref "R227") (pin "1") (pinfunction "1_1") (pintype "passive"))
      (node (ref "U25") (pin "4") (pinfunction "FB_4") (pintype "passive"))
    )
    (net (code "37") (name "Net-(U25-SW)") (class "Default")
      (node (ref "C156") (pin "2") (pinfunction "2_2") (pintype "passive"))
      (node (ref "L16") (pin "1") (pinfunction "1_1") (pintype "passive"))
      (node (ref "U25") (pin "2") (pinfunction "SW_2") (pintype "passive"))
    )
    (net (code "38") (name "Net-(U26-IREF)") (class "Default")
      (node (ref "R234") (pin "1") (pinfunction "1_1") (pintype "passive"))
      (node (ref "U26") (pin "10") (pinfunction "IREF_10") (pintype "passive"))
    )
    (net (code "39") (name "Net-(U26-S0)") (class "Default")
      (node (ref "R226") (pin "2") (pinfunction "2_2") (pintype "passive"))
      (node (ref "U26") (pin "2") (pinfunction "S0_2") (pintype "passive"))
    )
    (net (code "40") (name "Net-(U26-S1)") (class "Default")
      (node (ref "R225") (pin "2") (pinfunction "2_2") (pintype "passive"))
      (node (ref "U26") (pin "3") (pinfunction "S1_3") (pintype "passive"))
    )
    (net (code "41") (name "Net-(U26-S2)") (class "Default")
      (node (ref "R233") (pin "1") (pinfunction "1_1") (pintype "passive"))
      (node (ref "U26") (pin "4") (pinfunction "S2_4") (pintype "passive"))
    )
    (net (code "42") (name "Net-(U26-VDDODA)") (class "Default")
      (node (ref "C166") (pin "1") (pinfunction "1_1") (pintype "passive"))
      (node (ref "C167") (pin "1") (pinfunction "1_1") (pintype "passive"))
      (node (ref "R235") (pin "2") (pinfunction "2_2") (pintype "passive"))
      (node (ref "U26") (pin "15") (pinfunction "VDDODA_15") (pintype "passive"))
    )
    (net (code "43") (name "Net-(U26-X1)") (class "Default")
      (node (ref "C164") (pin "1") (pinfunction "1_1") (pintype "passive"))
      (node (ref "U26") (pin "5") (pinfunction "X1_5") (pintype "passive"))
      (node (ref "Y4") (pin "1") (pinfunction "1_1") (pintype "passive"))
    )
    (net (code "44") (name "Net-(U26-X2)") (class "Default")
      (node (ref "R230") (pin "2") (pinfunction "2_2") (pintype "passive"))
      (node (ref "U26") (pin "6") (pinfunction "X2_6") (pintype "passive"))
    )
    (net (code "45") (name "Net-(U27-EN)") (class "Default")
      (node (ref "R246") (pin "1") (pinfunction "1_1") (pintype "passive"))
      (node (ref "U27") (pin "3") (pinfunction "EN_3") (pintype "passive"))
    )
    (net (code "46") (name "Net-(U27-NC)") (class "Default")
      (node (ref "C188") (pin "1") (pinfunction "1_1") (pintype "passive"))
      (node (ref "U27") (pin "4") (pinfunction "NC_4") (pintype "passive"))
    )
    (net (code "47") (name "Net-(U28-BOOT)") (class "Default")
      (node (ref "C179") (pin "1") (pinfunction "1_1") (pintype "passive"))
      (node (ref "U28") (pin "6") (pinfunction "BOOT_6") (pintype "passive"))
    )
    (net (code "48") (name "Net-(U28-EN)") (class "Default")
      (node (ref "R251") (pin "1") (pinfunction "1_1") (pintype "passive"))
      (node (ref "R252") (pin "1") (pinfunction "1_1") (pintype "passive"))
      (node (ref "U28") (pin "5") (pinfunction "EN_5") (pintype "passive"))
    )
    (net (code "49") (name "Net-(U28-FB)") (class "Default")
      (node (ref "C194") (pin "1") (pinfunction "1_1") (pintype "passive"))
      (node (ref "R249") (pin "1") (pinfunction "1_1") (pintype "passive"))
      (node (ref "R250") (pin "1") (pinfunction "1_1") (pintype "passive"))
      (node (ref "U28") (pin "4") (pinfunction "FB_4") (pintype "passive"))
    )
    (net (code "50") (name "Net-(U28-SW)") (class "Default")
      (node (ref "C179") (pin "2") (pinfunction "2_2") (pintype "passive"))
      (node (ref "L17") (pin "1") (pinfunction "1_1") (pintype "passive"))
      (node (ref "U28") (pin "2") (pinfunction "SW_2") (pintype "passive"))
    )
    (net (code "51") (name "PCIE30X2_CLKREQN_M1") (class "Default")
      (node (ref "R248") (pin "1") (pinfunction "1_1") (pintype "passive"))
    )
    (net (code "52") (name "PCIE30X2_PERSTN_M1") (class "Default")
      (node (ref "J20") (pin "A11") (pinfunction "PERST#_A11") (pintype "passive"))
    )
    (net (code "53") (name "PCIE30X2_PRSNTn") (class "Default")
      (node (ref "R137") (pin "1") (pinfunction "1_1") (pintype "passive"))
    )
    (net (code "54") (name "PCIE30X2_WAKEN_M1") (class "Default")
      (node (ref "R247") (pin "1") (pinfunction "1_1") (pintype "passive"))
    )
    (net (code "55") (name "PCIE30X4_CLKREQN_M1") (class "Default")
      (node (ref "J19") (pin "52") (pinfunction "CLKREQ#_52") (pintype "passive"))
    )
    (net (code "56") (name "PCIE30X4_PERSTN_M1") (class "Default")
      (node (ref "J19") (pin "50") (pinfunction "PERST#_50") (pintype "passive"))
    )
    (net (code "57") (name "PCIE30X4_WAKEN_M1") (class "Default")
      (node (ref "J19") (pin "54") (pinfunction "PEWAKE#_54") (pintype "passive"))
    )
    (net (code "58") (name "PCIE30_PORT0_REF_CLKN") (class "Default")
      (node (ref "R217") (pin "2") (pinfunction "2_2") (pintype "passive"))
      (node (ref "R219") (pin "1") (pinfunction "1_1") (pintype "passive"))
    )
    (net (code "59") (name "PCIE30_PORT0_REF_CLKP") (class "Default")
      (node (ref "R216") (pin "2") (pinfunction "2_2") (pintype "passive"))
      (node (ref "R220") (pin "1") (pinfunction "1_1") (pintype "passive"))
    )
    (net (code "60") (name "PCIE30_PORT0_RX0N") (class "Default")
      (node (ref "J19") (pin "41") (pinfunction "SATA-/B+/PERn0_41") (pintype "passive"))
    )
    (net (code "61") (name "PCIE30_PORT0_RX0P") (class "Default")
      (node (ref "J19") (pin "43") (pinfunction "SATA-/B-/PERp0_43") (pintype "passive"))
    )
    (net (code "62") (name "PCIE30_PORT0_RX1N") (class "Default")
      (node (ref "J19") (pin "29") (pinfunction "PERn1_29") (pintype "passive"))
    )
    (net (code "63") (name "PCIE30_PORT0_RX1P") (class "Default")
      (node (ref "J19") (pin "31") (pinfunction "PERp1_31") (pintype "passive"))
    )
    (net (code "64") (name "PCIE30_PORT0_TX0N") (class "Default")
      (node (ref "C177") (pin "1") (pinfunction "1_1") (pintype "passive"))
    )
    (net (code "65") (name "PCIE30_PORT0_TX0P") (class "Default")
      (node (ref "C178") (pin "1") (pinfunction "1_1") (pintype "passive"))
    )
    (net (code "66") (name "PCIE30_PORT0_TX1N") (class "Default")
      (node (ref "C175") (pin "1") (pinfunction "1_1") (pintype "passive"))
    )
    (net (code "67") (name "PCIE30_PORT0_TX1P") (class "Default")
      (node (ref "C176") (pin "1") (pinfunction "1_1") (pintype "passive"))
    )
    (net (code "68") (name "PCIE30_PORT1_REF_CLKN") (class "Default")
      (node (ref "R243") (pin "2") (pinfunction "2_2") (pintype "passive"))
      (node (ref "R244") (pin "1") (pinfunction "1_1") (pintype "passive"))
    )
    (net (code "69") (name "PCIE30_PORT1_REF_CLKP") (class "Default")
      (node (ref "R242") (pin "2") (pinfunction "2_2") (pintype "passive"))
      (node (ref "R245") (pin "1") (pinfunction "1_1") (pintype "passive"))
    )
    (net (code "70") (name "PCIE30_PORT1_RX0N") (class "Default")
      (node (ref "J20") (pin "A17") (pinfunction "PERn0_A17") (pintype "passive"))
    )
    (net (code "71") (name "PCIE30_PORT1_RX0P") (class "Default")
      (node (ref "J20") (pin "A16") (pinfunction "PERp0_A16") (pintype "passive"))
    )
    (net (code "72") (name "PCIE30_PORT1_RX1N") (class "Default")
      (node (ref "J20") (pin "A22") (pinfunction "PERn1_A22") (pintype "passive"))
    )
    (net (code "73") (name "PCIE30_PORT1_RX1P") (class "Default")
      (node (ref "J20") (pin "A21") (pinfunction "PERp1_A21") (pintype "passive"))
    )
    (net (code "74") (name "PCIE30_PORT1_TX0N") (class "Default")
      (node (ref "C190") (pin "1") (pinfunction "1_1") (pintype "passive"))
    )
    (net (code "75") (name "PCIE30_PORT1_TX0P") (class "Default")
      (node (ref "C189") (pin "1") (pinfunction "1_1") (pintype "passive"))
    )
    (net (code "76") (name "PCIE30_PORT1_TX1N") (class "Default")
      (node (ref "C192") (pin "1") (pinfunction "1_1") (pintype "passive"))
    )
    (net (code "77") (name "PCIE30_PORT1_TX1P") (class "Default")
      (node (ref "C191") (pin "1") (pinfunction "1_1") (pintype "passive"))
    )
    (net (code "78") (name "PCIEx4_PWR_EN") (class "Default")
      (node (ref "R251") (pin "2") (pinfunction "2_2") (pintype "passive"))
      (node (ref "R256") (pin "1") (pinfunction "1_1") (pintype "passive"))
    )
    (net (code "79") (name "VCC3V3_PCIECLK") (class "Default")
      (node (ref "C162") (pin "1") (pinfunction "1_1") (pintype "passive"))
      (node (ref "C163") (pin "1") (pinfunction "1_1") (pintype "passive"))
      (node (ref "C168") (pin "1") (pinfunction "1_1") (pintype "passive"))
      (node (ref "C186") (pin "1") (pinfunction "1_1") (pintype "passive"))
      (node (ref "C187") (pin "1") (pinfunction "1_1") (pintype "passive"))
      (node (ref "R223") (pin "1") (pinfunction "1_1") (pintype "passive"))
      (node (ref "R224") (pin "1") (pinfunction "1_1") (pintype "passive"))
      (node (ref "R225") (pin "1") (pinfunction "1_1") (pintype "passive"))
      (node (ref "R226") (pin "1") (pinfunction "1_1") (pintype "passive"))
      (node (ref "R235") (pin "1") (pinfunction "1_1") (pintype "passive"))
      (node (ref "U26") (pin "1") (pinfunction "VDDXD_1") (pintype "passive"))
      (node (ref "U27") (pin "5") (pinfunction "OUT_5") (pintype "passive"))
    )
    (net (code "80") (name "VCC3V3_PCIEx4") (class "Default")
      (node (ref "C180") (pin "1") (pinfunction "1_1") (pintype "passive"))
      (node (ref "C193") (pin "1") (pinfunction "1_1") (pintype "passive"))
      (node (ref "C194") (pin "2") (pinfunction "2_2") (pintype "passive"))
      (node (ref "J20") (pin "A10") (pinfunction "+3.3V_3_A10") (pintype "passive"))
      (node (ref "J20") (pin "A9") (pinfunction "+3.3V_2_A9") (pintype "passive"))
      (node (ref "J20") (pin "B10") (pinfunction "3.3VAUX_B10") (pintype "passive"))
      (node (ref "J20") (pin "B8") (pinfunction "+3.3V_1_B8") (pintype "passive"))
      (node (ref "L17") (pin "2") (pinfunction "2_2") (pintype "passive"))
      (node (ref "R249") (pin "2") (pinfunction "2_2") (pintype "passive"))
    )
    (net (code "81") (name "VCC12V_PCIEx4") (class "Default")
      (node (ref "C197") (pin "1") (pinfunction "1_1") (pintype "passive"))
      (node (ref "C198") (pin "1") (pinfunction "1_1") (pintype "passive"))
      (node (ref "J20") (pin "A2") (pinfunction "+12V_4_A2") (pintype "passive"))
      (node (ref "J20") (pin "A3") (pinfunction "+12V_5_A3") (pintype "passive"))
      (node (ref "J20") (pin "B1") (pinfunction "+12V_1_B1") (pintype "passive"))
      (node (ref "J20") (pin "B2") (pinfunction "+12V_2_B2") (pintype "passive"))
      (node (ref "J20") (pin "B3") (pinfunction "+12V_3_B3") (pintype "passive"))
      (node (ref "Q30") (pin "3") (pinfunction "DRAIN_3") (pintype "passive"))
    )
    (net (code "82") (name "VCC_3V3_S0") (class "Default")
      (node (ref "R246") (pin "2") (pinfunction "2_2") (pintype "passive"))
      (node (ref "R328") (pin "1") (pinfunction "1_1") (pintype "passive"))
    )
    (net (code "83") (name "VCC_5V0_S0") (class "Default")
      (node (ref "C184") (pin "1") (pinfunction "1_1") (pintype "passive"))
      (node (ref "C185") (pin "1") (pinfunction "1_1") (pintype "passive"))
      (node (ref "U27") (pin "1") (pinfunction "IN_1") (pintype "passive"))
    )
    (net (code "84") (name "VCC_12V") (class "Default")
      (node (ref "C160") (pin "1") (pinfunction "1_1") (pintype "passive"))
      (node (ref "C161") (pin "1") (pinfunction "1_1") (pintype "passive"))
      (node (ref "C195") (pin "1") (pinfunction "1_1") (pintype "passive"))
      (node (ref "C196") (pin "1") (pinfunction "1_1") (pintype "passive"))
      (node (ref "Q30") (pin "2") (pinfunction "SOURCE_2") (pintype "passive"))
      (node (ref "R255") (pin "1") (pinfunction "1_1") (pintype "passive"))
      (node (ref "U25") (pin "3") (pinfunction "VIN_3") (pintype "passive"))
      (node (ref "U28") (pin "3") (pinfunction "VIN_3") (pintype "passive"))
    )
    (net (code "85") (name "unconnected-(J19-CONFIG_1-Pad69)") (class "Default")
      (node (ref "J19") (pin "69") (pinfunction "CONFIG_1_69") (pintype "passive+no_connect"))
    )
    (net (code "86") (name "unconnected-(J19-MFG1-Pad56)") (class "Default")
      (node (ref "J19") (pin "56") (pinfunction "MFG1_56") (pintype "passive+no_connect"))
    )
    (net (code "87") (name "unconnected-(J19-MFG2-Pad58)") (class "Default")
      (node (ref "J19") (pin "58") (pinfunction "MFG2_58") (pintype "passive+no_connect"))
    )
    (net (code "88") (name "unconnected-(J19-N{slash}A_1-Pad6)") (class "Default")
      (node (ref "J19") (pin "6") (pinfunction "N/A_1_6") (pintype "passive+no_connect"))
    )
    (net (code "89") (name "unconnected-(J19-N{slash}A_2-Pad8)") (class "Default")
      (node (ref "J19") (pin "8") (pinfunction "N/A_2_8") (pintype "passive+no_connect"))
    )
    (net (code "90") (name "unconnected-(J19-N{slash}A_3-Pad20)") (class "Default")
      (node (ref "J19") (pin "20") (pinfunction "N/A_3_20") (pintype "passive+no_connect"))
    )
    (net (code "91") (name "unconnected-(J19-N{slash}A_4-Pad22)") (class "Default")
      (node (ref "J19") (pin "22") (pinfunction "N/A_4_22") (pintype "passive+no_connect"))
    )
    (net (code "92") (name "unconnected-(J19-N{slash}A_5-Pad24)") (class "Default")
      (node (ref "J19") (pin "24") (pinfunction "N/A_5_24") (pintype "passive+no_connect"))
    )
    (net (code "93") (name "unconnected-(J19-N{slash}A_6-Pad26)") (class "Default")
      (node (ref "J19") (pin "26") (pinfunction "N/A_6_26") (pintype "passive+no_connect"))
    )
    (net (code "94") (name "unconnected-(J19-N{slash}A_7-Pad28)") (class "Default")
      (node (ref "J19") (pin "28") (pinfunction "N/A_7_28") (pintype "passive+no_connect"))
    )
    (net (code "95") (name "unconnected-(J19-N{slash}A_8-Pad30)") (class "Default")
      (node (ref "J19") (pin "30") (pinfunction "N/A_8_30") (pintype "passive+no_connect"))
    )
    (net (code "96") (name "unconnected-(J19-N{slash}A_9-Pad32)") (class "Default")
      (node (ref "J19") (pin "32") (pinfunction "N/A_9_32") (pintype "passive+no_connect"))
    )
    (net (code "97") (name "unconnected-(J19-N{slash}A_10-Pad34)") (class "Default")
      (node (ref "J19") (pin "34") (pinfunction "N/A_10_34") (pintype "passive+no_connect"))
    )
    (net (code "98") (name "unconnected-(J19-N{slash}A_11-Pad36)") (class "Default")
      (node (ref "J19") (pin "36") (pinfunction "N/A_11_36") (pintype "passive+no_connect"))
    )
    (net (code "99") (name "unconnected-(J19-N{slash}A_12-Pad40)") (class "Default")
      (node (ref "J19") (pin "40") (pinfunction "N/A_12_40") (pintype "passive+no_connect"))
    )
    (net (code "100") (name "unconnected-(J19-N{slash}A_13-Pad42)") (class "Default")
      (node (ref "J19") (pin "42") (pinfunction "N/A_13_42") (pintype "passive+no_connect"))
    )
    (net (code "101") (name "unconnected-(J19-N{slash}A_14-Pad44)") (class "Default")
      (node (ref "J19") (pin "44") (pinfunction "N/A_14_44") (pintype "passive+no_connect"))
    )
    (net (code "102") (name "unconnected-(J19-N{slash}A_15-Pad46)") (class "Default")
      (node (ref "J19") (pin "46") (pinfunction "N/A_15_46") (pintype "passive+no_connect"))
    )
    (net (code "103") (name "unconnected-(J19-N{slash}A_16-Pad48)") (class "Default")
      (node (ref "J19") (pin "48") (pinfunction "N/A_16_48") (pintype "passive+no_connect"))
    )
    (net (code "104") (name "unconnected-(J19-N{slash}A_17-Pad67)") (class "Default")
      (node (ref "J19") (pin "67") (pinfunction "N/A_17_67") (pintype "passive+no_connect"))
    )
    (net (code "105") (name "unconnected-(J19-PERn2-Pad17)") (class "Default")
      (node (ref "J19") (pin "17") (pinfunction "PERn2_17") (pintype "passive+no_connect"))
    )
    (net (code "106") (name "unconnected-(J19-PERn3-Pad5)") (class "Default")
      (node (ref "J19") (pin "5") (pinfunction "PERn3_5") (pintype "passive+no_connect"))
    )
    (net (code "107") (name "unconnected-(J19-PERp2-Pad19)") (class "Default")
      (node (ref "J19") (pin "19") (pinfunction "PERp2_19") (pintype "passive+no_connect"))
    )
    (net (code "108") (name "unconnected-(J19-PERp3-Pad7)") (class "Default")
      (node (ref "J19") (pin "7") (pinfunction "PERp3_7") (pintype "passive+no_connect"))
    )
    (net (code "109") (name "unconnected-(J19-PETn2-Pad23)") (class "Default")
      (node (ref "J19") (pin "23") (pinfunction "PETn2_23") (pintype "passive+no_connect"))
    )
    (net (code "110") (name "unconnected-(J19-PETn3-Pad11)") (class "Default")
      (node (ref "J19") (pin "11") (pinfunction "PETn3_11") (pintype "passive+no_connect"))
    )
    (net (code "111") (name "unconnected-(J19-PETp2-Pad25)") (class "Default")
      (node (ref "J19") (pin "25") (pinfunction "PETp2_25") (pintype "passive+no_connect"))
    )
    (net (code "112") (name "unconnected-(J19-PETp3-Pad13)") (class "Default")
      (node (ref "J19") (pin "13") (pinfunction "PETp3_13") (pintype "passive+no_connect"))
    )
    (net (code "113") (name "unconnected-(J19-SUSCLK-Pad68)") (class "Default")
      (node (ref "J19") (pin "68") (pinfunction "SUSCLK_68") (pintype "passive+no_connect"))
    )
    (net (code "114") (name "unconnected-(J20-JTAG_TCK-PadA5)") (class "Default")
      (node (ref "J20") (pin "A5") (pinfunction "JTAG_TCK_A5") (pintype "passive+no_connect"))
    )
    (net (code "115") (name "unconnected-(J20-JTAG_TDI-PadA6)") (class "Default")
      (node (ref "J20") (pin "A6") (pinfunction "JTAG_TDI_A6") (pintype "passive+no_connect"))
    )
    (net (code "116") (name "unconnected-(J20-JTAG_TDO-PadA7)") (class "Default")
      (node (ref "J20") (pin "A7") (pinfunction "JTAG_TDO_A7") (pintype "passive+no_connect"))
    )
    (net (code "117") (name "unconnected-(J20-JTAG_TMS-PadA8)") (class "Default")
      (node (ref "J20") (pin "A8") (pinfunction "JTAG_TMS_A8") (pintype "passive+no_connect"))
    )
    (net (code "118") (name "unconnected-(J20-JTAG_TRST-PadB9)") (class "Default")
      (node (ref "J20") (pin "B9") (pinfunction "JTAG_TRST_B9") (pintype "passive+no_connect"))
    )
    (net (code "119") (name "unconnected-(J20-PERn2-PadA26)") (class "Default")
      (node (ref "J20") (pin "A26") (pinfunction "PERn2_A26") (pintype "passive+no_connect"))
    )
    (net (code "120") (name "unconnected-(J20-PERn3-PadA30)") (class "Default")
      (node (ref "J20") (pin "A30") (pinfunction "PERn3_A30") (pintype "passive+no_connect"))
    )
    (net (code "121") (name "unconnected-(J20-PERp2-PadA25)") (class "Default")
      (node (ref "J20") (pin "A25") (pinfunction "PERp2_A25") (pintype "passive+no_connect"))
    )
    (net (code "122") (name "unconnected-(J20-PERp3-PadA29)") (class "Default")
      (node (ref "J20") (pin "A29") (pinfunction "PERp3_A29") (pintype "passive+no_connect"))
    )
    (net (code "123") (name "unconnected-(J20-PETn2-PadB24)") (class "Default")
      (node (ref "J20") (pin "B24") (pinfunction "PETn2_B24") (pintype "passive+no_connect"))
    )
    (net (code "124") (name "unconnected-(J20-PETn3-PadB28)") (class "Default")
      (node (ref "J20") (pin "B28") (pinfunction "PETn3_B28") (pintype "passive+no_connect"))
    )
    (net (code "125") (name "unconnected-(J20-PETp2-PadB23)") (class "Default")
      (node (ref "J20") (pin "B23") (pinfunction "PETp2_B23") (pintype "passive+no_connect"))
    )
    (net (code "126") (name "unconnected-(J20-PETp3-PadB27)") (class "Default")
      (node (ref "J20") (pin "B27") (pinfunction "PETp3_B27") (pintype "passive+no_connect"))
    )
    (net (code "127") (name "unconnected-(J20-RSVD_A19-PadA19)") (class "Default")
      (node (ref "J20") (pin "A19") (pinfunction "RSVD_A19_A19") (pintype "passive+no_connect"))
    )
    (net (code "128") (name "unconnected-(J20-RSVD_A32-PadA32)") (class "Default")
      (node (ref "J20") (pin "A32") (pinfunction "RSVD_A32_A32") (pintype "passive+no_connect"))
    )
    (net (code "129") (name "unconnected-(J20-RSVD_B30-PadB30)") (class "Default")
      (node (ref "J20") (pin "B30") (pinfunction "RSVD_B30_B30") (pintype "passive+no_connect"))
    )
    (net (code "130") (name "unconnected-(J20-SMCLK-PadB5)") (class "Default")
      (node (ref "J20") (pin "B5") (pinfunction "SMCLK_B5") (pintype "passive+no_connect"))
    )
    (net (code "131") (name "unconnected-(J20-SMDAT-PadB6)") (class "Default")
      (node (ref "J20") (pin "B6") (pinfunction "SMDAT_B6") (pintype "passive+no_connect"))
    )
  )
)
